# ecg_board.net
KiCad netlist of a schematic drawn in EAGLE
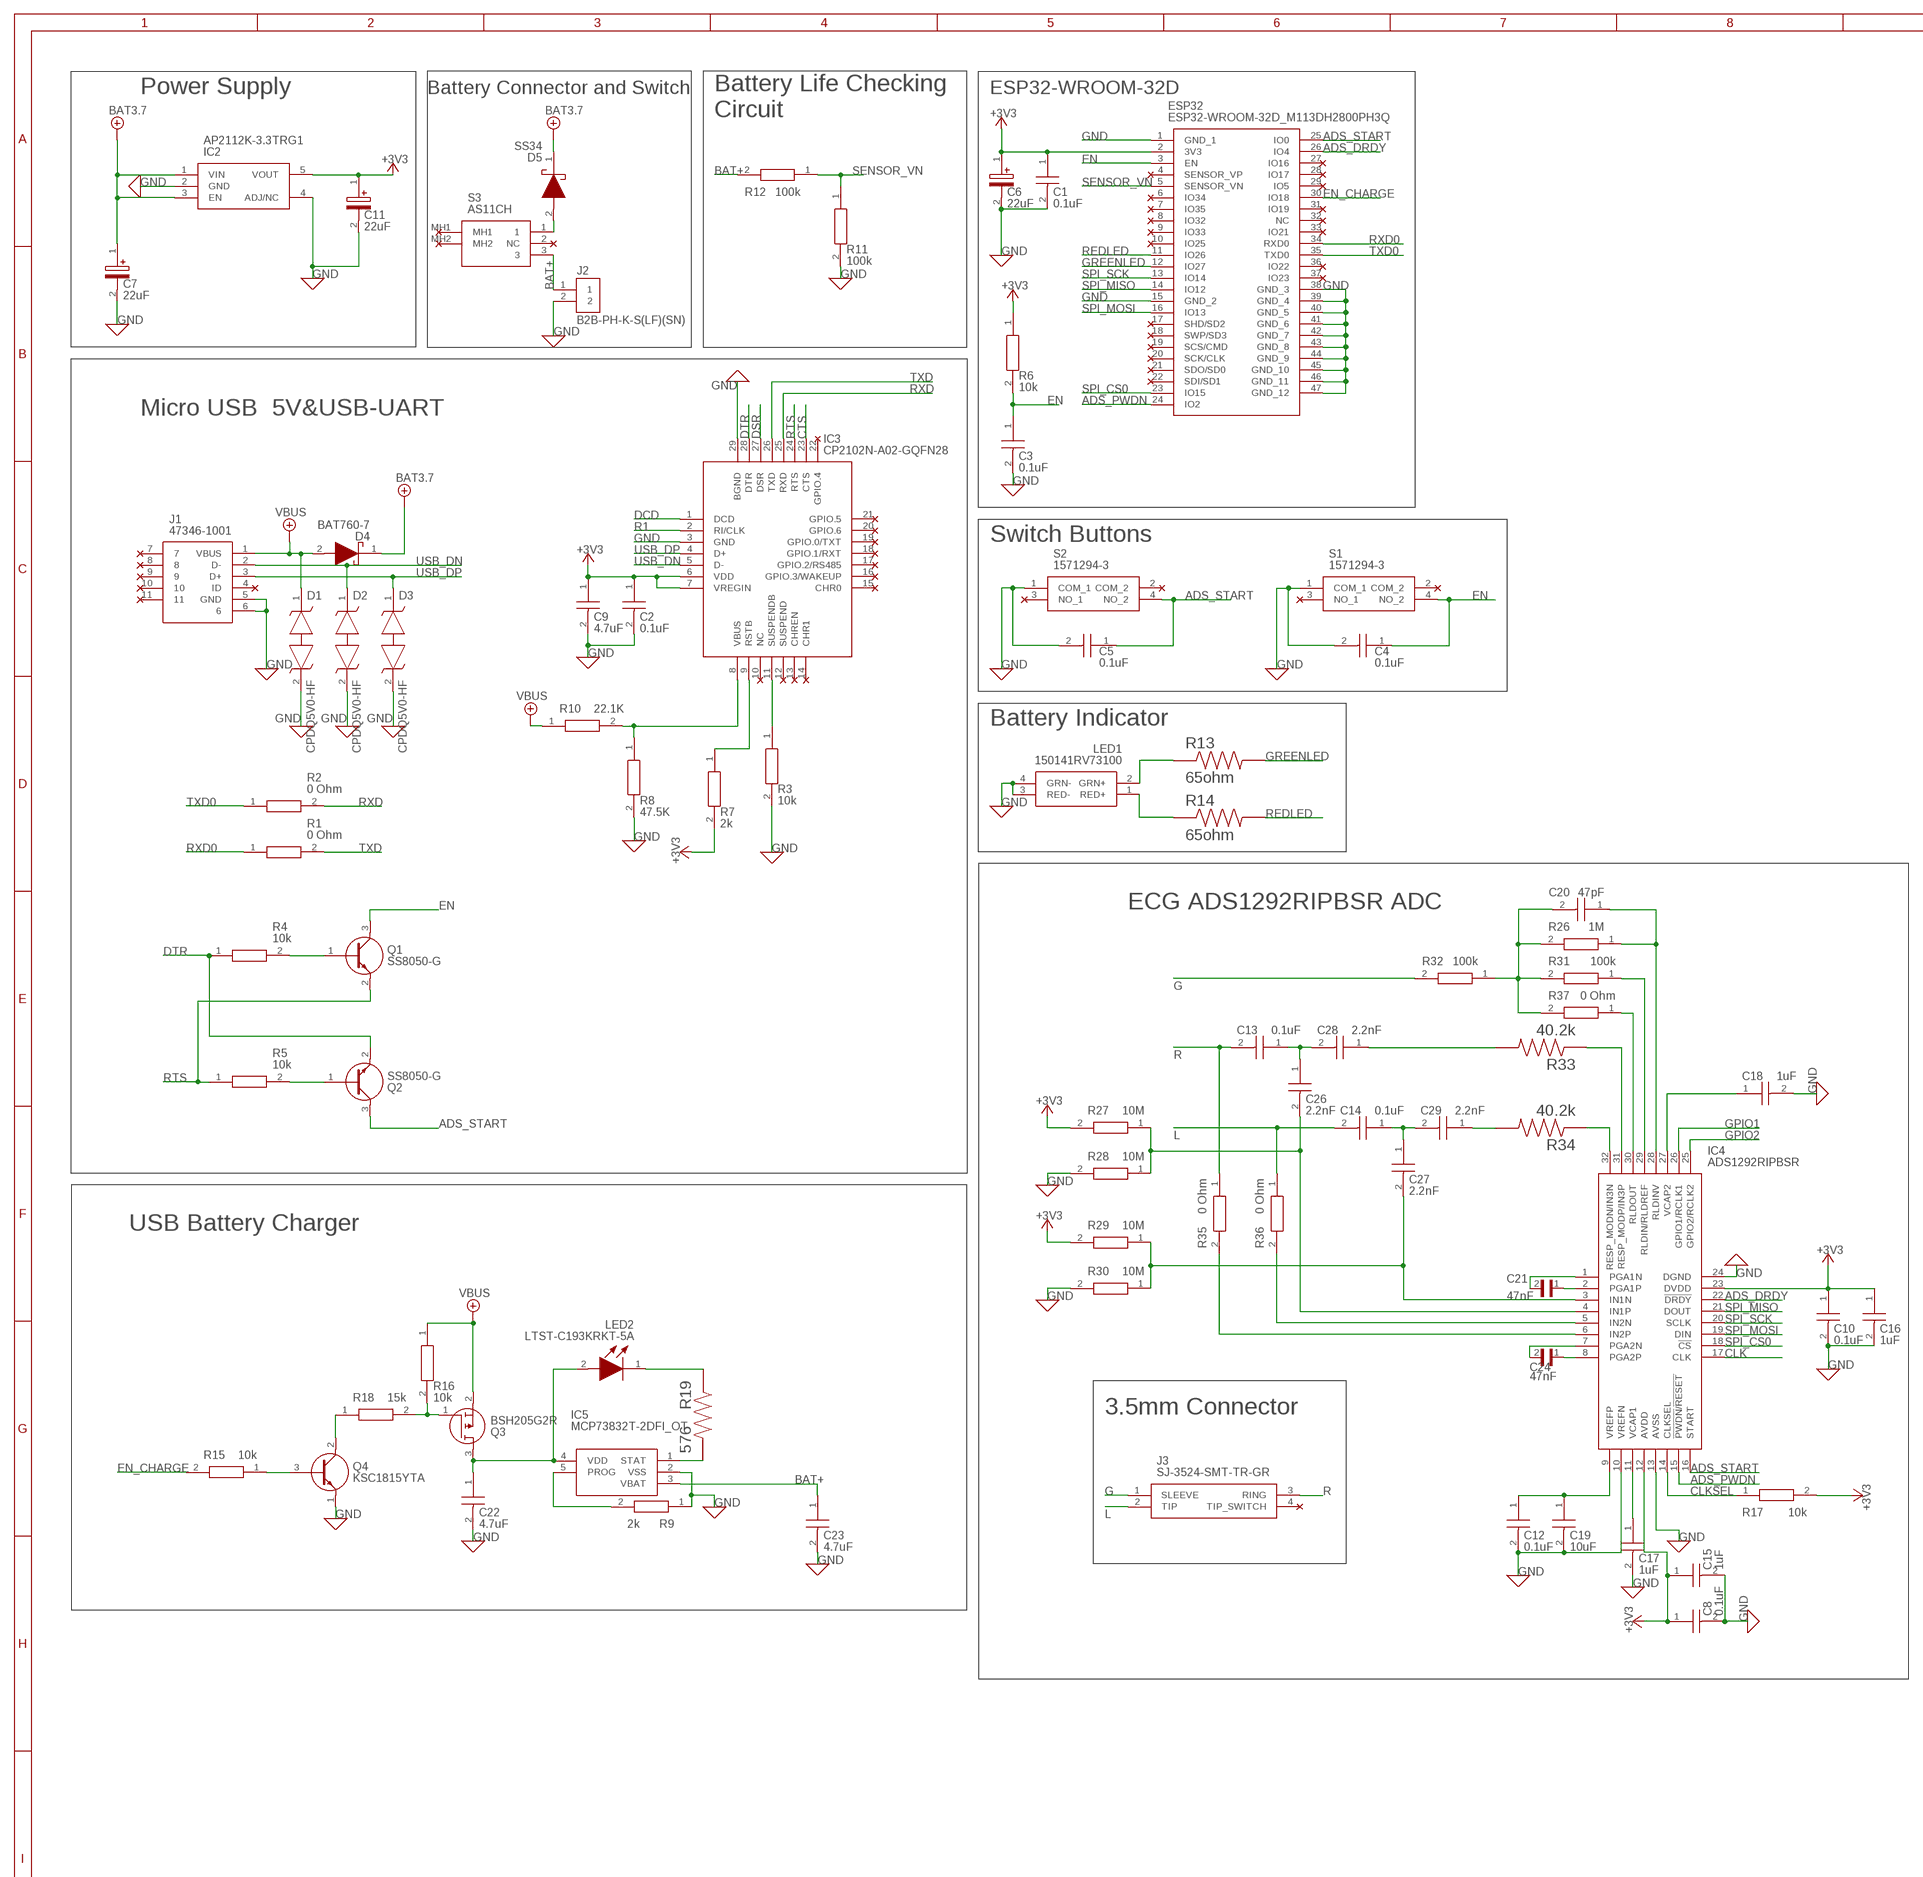
[diagram p0: schematic, sheet 1, part 1 of 2]
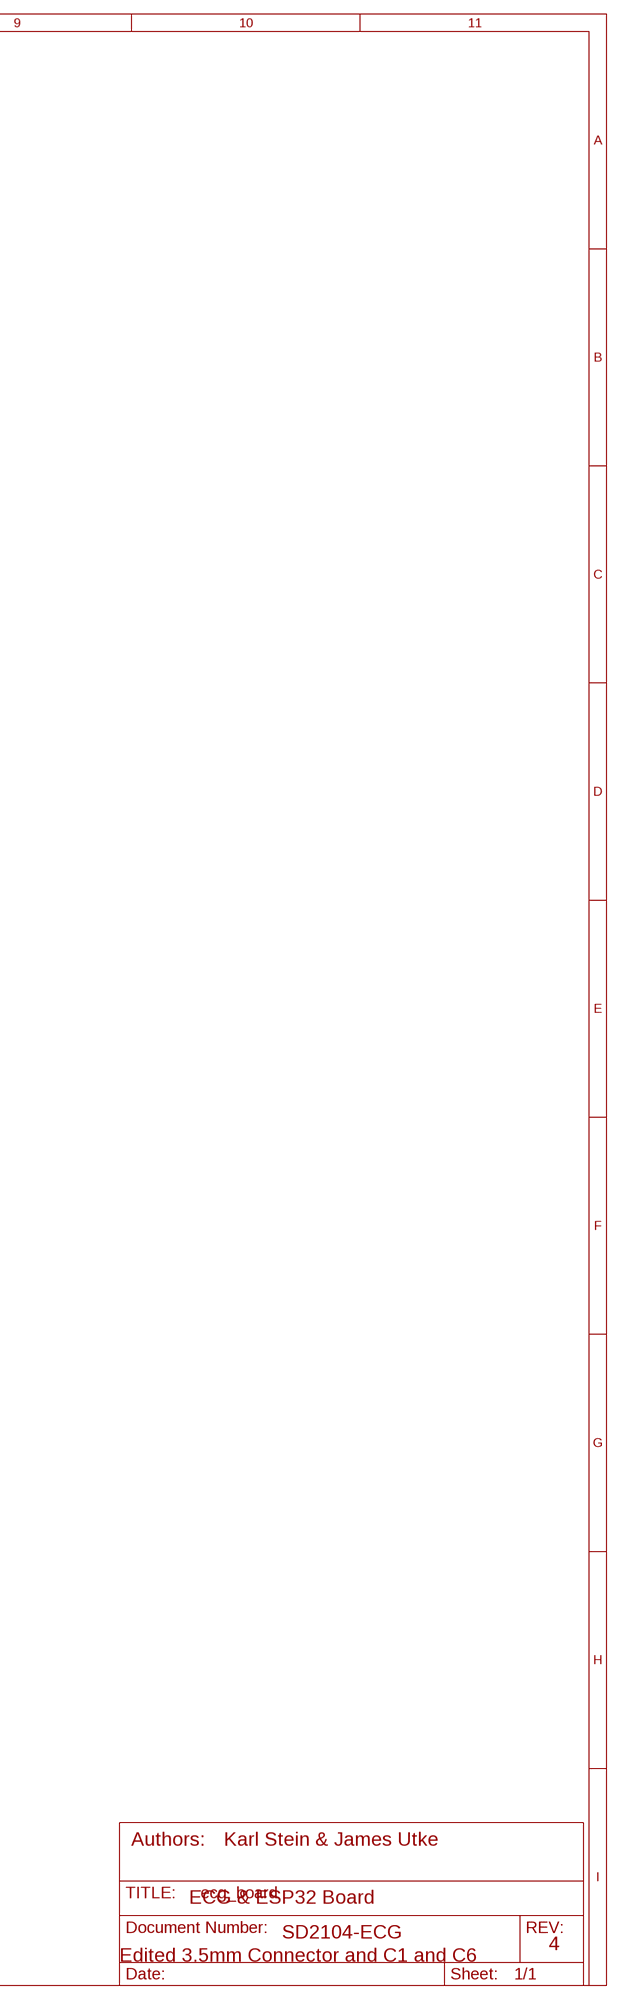
[diagram p1: schematic, sheet 1, part 2 of 2]

(export (version "E")
  (design (tool "Eeschema 10.0.6"))
  (components
    (comp (ref "C1")
      (value "0.1uF")
      (footprint "eagle-import:CAPC2012X88N")
      (fields
        (field (name "MANUFACTURER_PART_NUMBER") "C0805C104K5RAC7411")
        (field (name "MOUSER_PART_NUMBER") "80-C0805C104K5RACLR")
      )
      (libsource (lib "eagle-import") (part "C0805C104K5RAC7411"))
    )
    (comp (ref "C2")
      (value "0.1uF")
      (footprint "eagle-import:CAPC2012X88N")
      (fields
        (field (name "MANUFACTURER_PART_NUMBER") "C0805C104K5RAC7411")
        (field (name "MOUSER_PART_NUMBER") "80-C0805C104K5RACLR")
      )
      (libsource (lib "eagle-import") (part "C0805C104K5RAC7411"))
    )
    (comp (ref "C3")
      (value "0.1uF")
      (footprint "eagle-import:CAPC2012X88N")
      (fields
        (field (name "MANUFACTURER_PART_NUMBER") "C0805C104K5RAC7411")
        (field (name "MOUSER_PART_NUMBER") "80-C0805C104K5RACLR")
      )
      (libsource (lib "eagle-import") (part "C0805C104K5RAC7411"))
    )
    (comp (ref "C4")
      (value "0.1uF")
      (footprint "eagle-import:CAPC2012X88N")
      (fields
        (field (name "MANUFACTURER_PART_NUMBER") "C0805C104K5RAC7411")
        (field (name "MOUSER_PART_NUMBER") "80-C0805C104K5RACLR")
      )
      (libsource (lib "eagle-import") (part "C0805C104K5RAC7411"))
    )
    (comp (ref "C5")
      (value "0.1uF")
      (footprint "eagle-import:CAPC2012X88N")
      (fields
        (field (name "MANUFACTURER_PART_NUMBER") "C0805C104K5RAC7411")
        (field (name "MOUSER_PART_NUMBER") "80-C0805C104K5RACLR")
      )
      (libsource (lib "eagle-import") (part "C0805C104K5RAC7411"))
    )
    (comp (ref "C6")
      (value "22uF")
      (footprint "eagle-import:CAPPC1609X90N")
      (fields
        (field (name "MANUFACTURER_PART_NUMBER") "F381A226MMAAXE")
        (field (name "MOUSER_PART_NUMBER") "581-F381A226MMAAXE")
      )
      (libsource (lib "eagle-import") (part "F381A226MMAAXE"))
    )
    (comp (ref "C7")
      (value "22uF")
      (footprint "eagle-import:CAPPC1609X90N")
      (fields
        (field (name "MANUFACTURER_PART_NUMBER") "F381A226MMAAXE")
        (field (name "MOUSER_PART_NUMBER") "581-F381A226MMAAXE")
      )
      (libsource (lib "eagle-import") (part "F381A226MMAAXE"))
    )
    (comp (ref "C8")
      (value "0.1uF")
      (footprint "eagle-import:CAPC2012X88N")
      (fields
        (field (name "MANUFACTURER_PART_NUMBER") "C0805C104K5RAC7411")
        (field (name "MOUSER_PART_NUMBER") "80-C0805C104K5RACLR")
      )
      (libsource (lib "eagle-import") (part "C0805C104K5RAC7411"))
    )
    (comp (ref "C9")
      (value "4.7uF")
      (footprint "eagle-import:CAPC2114X145N")
      (fields
        (field (name "MANUFACTURER_PART_NUMBER") "JMK212B7475KGHT")
        (field (name "MOUSER_PART_NUMBER") "963-JMK212B7475KGHT")
      )
      (libsource (lib "eagle-import") (part "JMK212B7475KGHT"))
    )
    (comp (ref "C10")
      (value "0.1uF")
      (footprint "eagle-import:CAPC2012X88N")
      (fields
        (field (name "MANUFACTURER_PART_NUMBER") "C0805C104K5RAC7411")
        (field (name "MOUSER_PART_NUMBER") "80-C0805C104K5RACLR")
      )
      (libsource (lib "eagle-import") (part "C0805C104K5RAC7411"))
    )
    (comp (ref "C11")
      (value "22uF")
      (footprint "eagle-import:CAPPC1609X90N")
      (fields
        (field (name "MANUFACTURER_PART_NUMBER") "F381A226MMAAXE")
        (field (name "MOUSER_PART_NUMBER") "581-F381A226MMAAXE")
      )
      (libsource (lib "eagle-import") (part "F381A226MMAAXE"))
    )
    (comp (ref "C12")
      (value "0.1uF")
      (footprint "eagle-import:CAPC2012X88N")
      (fields
        (field (name "MANUFACTURER_PART_NUMBER") "C0805C104K5RAC7411")
        (field (name "MOUSER_PART_NUMBER") "80-C0805C104K5RACLR")
      )
      (libsource (lib "eagle-import") (part "C0805C104K5RAC7411"))
    )
    (comp (ref "C13")
      (value "0.1uF")
      (footprint "eagle-import:CAPC2012X88N")
      (fields
        (field (name "MANUFACTURER_PART_NUMBER") "C0805C104K5RAC7411")
        (field (name "MOUSER_PART_NUMBER") "80-C0805C104K5RACLR")
      )
      (libsource (lib "eagle-import") (part "C0805C104K5RAC7411"))
    )
    (comp (ref "C14")
      (value "0.1uF")
      (footprint "eagle-import:CAPC2012X88N")
      (fields
        (field (name "MANUFACTURER_PART_NUMBER") "C0805C104K5RAC7411")
        (field (name "MOUSER_PART_NUMBER") "80-C0805C104K5RACLR")
      )
      (libsource (lib "eagle-import") (part "C0805C104K5RAC7411"))
    )
    (comp (ref "C15")
      (value "1uF")
      (footprint "eagle-import:CAPC2012X100N")
      (fields
        (field (name "MANUFACTURER_PART_NUMBER") "C0805X105K8RAC7210")
        (field (name "MOUSER_PART_NUMBER") "80-C0805X105K8RACLR")
      )
      (libsource (lib "eagle-import") (part "C0805X105K8RAC7210"))
    )
    (comp (ref "C16")
      (value "1uF")
      (footprint "eagle-import:CAPC2012X100N")
      (fields
        (field (name "MANUFACTURER_PART_NUMBER") "C0805X105K8RAC7210")
        (field (name "MOUSER_PART_NUMBER") "80-C0805X105K8RACLR")
      )
      (libsource (lib "eagle-import") (part "C0805X105K8RAC7210"))
    )
    (comp (ref "C17")
      (value "1uF")
      (footprint "eagle-import:CAPC2012X100N")
      (fields
        (field (name "MANUFACTURER_PART_NUMBER") "C0805X105K8RAC7210")
        (field (name "MOUSER_PART_NUMBER") "80-C0805X105K8RACLR")
      )
      (libsource (lib "eagle-import") (part "C0805X105K8RAC7210"))
    )
    (comp (ref "C18")
      (value "1uF")
      (footprint "eagle-import:CAPC2012X100N")
      (fields
        (field (name "MANUFACTURER_PART_NUMBER") "C0805X105K8RAC7210")
        (field (name "MOUSER_PART_NUMBER") "80-C0805X105K8RACLR")
      )
      (libsource (lib "eagle-import") (part "C0805X105K8RAC7210"))
    )
    (comp (ref "C19")
      (value "10uF")
      (footprint "eagle-import:CAPC2012X135N")
      (fields
        (field (name "MANUFACTURER_PART_NUMBER") "TMK212BBJ106MGHT")
        (field (name "MOUSER_PART_NUMBER") "963-TMK212BBJ106MGHT")
      )
      (libsource (lib "eagle-import") (part "TMK212BBJ106MGHT"))
    )
    (comp (ref "C20")
      (value "47pF")
      (footprint "eagle-import:CAPC2012X95N")
      (fields
        (field (name "MANUFACTURER_PART_NUMBER") "CBR08C470J5GAC")
        (field (name "MOUSER_PART_NUMBER") "80-CBR08C470J5GAC")
      )
      (libsource (lib "eagle-import") (part "CBR08C470J5GAC"))
    )
    (comp (ref "C21")
      (value "47nF")
      (footprint "eagle-import:CAPC2012X140N")
      (fields
        (field (name "DIGI-KEY_PART_NUMBER") "399-C0805C473K1RECAUTOCT-ND")
        (field (name "MF") "KEMET")
        (field (name "MP") "C0805C473K1RECAUTO")
      )
      (libsource (lib "eagle-import") (part "C0805C473K1RECAUTO"))
    )
    (comp (ref "C22")
      (value "4.7uF")
      (footprint "eagle-import:CAPC2114X145N")
      (fields
        (field (name "MANUFACTURER_PART_NUMBER") "JMK212B7475KGHT")
        (field (name "MOUSER_PART_NUMBER") "963-JMK212B7475KGHT")
      )
      (libsource (lib "eagle-import") (part "JMK212B7475KGHT"))
    )
    (comp (ref "C23")
      (value "4.7uF")
      (footprint "eagle-import:CAPC2114X145N")
      (fields
        (field (name "MANUFACTURER_PART_NUMBER") "JMK212B7475KGHT")
        (field (name "MOUSER_PART_NUMBER") "963-JMK212B7475KGHT")
      )
      (libsource (lib "eagle-import") (part "JMK212B7475KGHT"))
    )
    (comp (ref "C24")
      (value "47nF")
      (footprint "eagle-import:CAPC2012X140N")
      (fields
        (field (name "DIGI-KEY_PART_NUMBER") "399-C0805C473K1RECAUTOCT-ND")
        (field (name "MF") "KEMET")
        (field (name "MP") "C0805C473K1RECAUTO")
      )
      (libsource (lib "eagle-import") (part "C0805C473K1RECAUTO"))
    )
    (comp (ref "C26")
      (value "2.2nF")
      (footprint "eagle-import:CAPC2012X100N")
      (fields
        (field (name "MANUFACTURER_PART_NUMBER") "C0805J222K1RACAUTO")
        (field (name "MOUSER_PART_NUMBER") "80-C0805J222K1RAUTO")
      )
      (libsource (lib "eagle-import") (part "C0805J222K1RACAUTO"))
    )
    (comp (ref "C27")
      (value "2.2nF")
      (footprint "eagle-import:CAPC2012X100N")
      (fields
        (field (name "MANUFACTURER_PART_NUMBER") "C0805J222K1RACAUTO")
        (field (name "MOUSER_PART_NUMBER") "80-C0805J222K1RAUTO")
      )
      (libsource (lib "eagle-import") (part "C0805J222K1RACAUTO"))
    )
    (comp (ref "C28")
      (value "2.2nF")
      (footprint "eagle-import:CAPC2012X100N")
      (fields
        (field (name "MANUFACTURER_PART_NUMBER") "C0805J222K1RACAUTO")
        (field (name "MOUSER_PART_NUMBER") "80-C0805J222K1RAUTO")
      )
      (libsource (lib "eagle-import") (part "C0805J222K1RACAUTO"))
    )
    (comp (ref "C29")
      (value "2.2nF")
      (footprint "eagle-import:CAPC2012X100N")
      (fields
        (field (name "MANUFACTURER_PART_NUMBER") "C0805J222K1RACAUTO")
        (field (name "MOUSER_PART_NUMBER") "80-C0805J222K1RAUTO")
      )
      (libsource (lib "eagle-import") (part "C0805J222K1RACAUTO"))
    )
    (comp (ref "D1")
      (value "CPDQ5V0-HF")
      (footprint "eagle-import:SODFL1006X40N")
      (fields (field (name "MOUSER_PART_NUMBER") "750-CPDQ5V0-HF"))
      (libsource (lib "eagle-import") (part "CPDQ5V0-HF"))
    )
    (comp (ref "D2")
      (value "CPDQ5V0-HF")
      (footprint "eagle-import:SODFL1006X40N")
      (fields (field (name "MOUSER_PART_NUMBER") "750-CPDQ5V0-HF"))
      (libsource (lib "eagle-import") (part "CPDQ5V0-HF"))
    )
    (comp (ref "D3")
      (value "CPDQ5V0-HF")
      (footprint "eagle-import:SODFL1006X40N")
      (fields (field (name "MOUSER_PART_NUMBER") "750-CPDQ5V0-HF"))
      (libsource (lib "eagle-import") (part "CPDQ5V0-HF"))
    )
    (comp (ref "D4")
      (value "BAT760-7")
      (footprint "eagle-import:SOD2513X120N")
      (fields (field (name "MOUSER_PART_NUMBER") "621-BAT760-7"))
      (libsource (lib "eagle-import") (part "BAT760-7"))
    )
    (comp (ref "D5")
      (value "SS34")
      (footprint "eagle-import:DIOM8059X256N")
      (fields (field (name "MOUSER_PART_NUMBER") "512-SS34"))
      (libsource (lib "eagle-import") (part "SS34"))
    )
    (comp (ref "ESP32")
      (value "ESP32-WROOM-32D_M113DH2800PH3Q")
      (footprint "eagle-import:ESP32WROOM32DM113DH2800PH3Q0")
      (fields
        (field (name "MANUFACTURER_PART_NUMBER") "ESP32-WROOM-32D(M113DH2800PH3Q0)")
        (field (name "MOUSER_PART_NUMBER") "356-ES32WROOM32D16MB")
      )
      (libsource (lib "eagle-import") (part "ESP32-WROOM-32D_M113DH2800PH3Q"))
    )
    (comp (ref "IC2")
      (value "AP2112K-3.3TRG1")
      (footprint "eagle-import:SOT95P282X130-5N")
      (fields (field (name "MOUSER_PART_NUMBER") "621-AP2112K-3.3TRG1"))
      (libsource (lib "eagle-import") (part "AP2112K-3.3TRG1"))
    )
    (comp (ref "IC3")
      (value "CP2102N-A02-GQFN28")
      (footprint "eagle-import:QFN50P500X500X80-29N")
      (fields (field (name "MOUSER_PART_NUMBER") "634-CP2102NA02GQFN28"))
      (libsource (lib "eagle-import") (part "CP2102N-A02-GQFN28"))
    )
    (comp (ref "IC4")
      (value "ADS1292RIPBSR")
      (footprint "eagle-import:QFP50P700X700X120-32N")
      (fields (field (name "MOUSER_PART_NUMBER") "595-ADS1292RIPBSR"))
      (libsource (lib "eagle-import") (part "ADS1292RIPBSR"))
    )
    (comp (ref "IC5")
      (value "MCP73832T-2DFI_OT")
      (footprint "eagle-import:SOT95P270X145-5N")
      (fields
        (field (name "MANUFACTURER_PART_NUMBER") "MCP73832T-2DFI/OT")
        (field (name "MOUSER_PART_NUMBER") "579-MCP73832T2DFI/OT")
      )
      (libsource (lib "eagle-import") (part "MCP73832T-2DFI_OT"))
    )
    (comp (ref "J1")
      (value "47346-1001")
      (footprint "eagle-import:473461001")
      (fields (field (name "MOUSER_PART_NUMBER") "538-47346-1001"))
      (libsource (lib "eagle-import") (part "47346-1001"))
    )
    (comp (ref "J2")
      (value "B2B-PH-K-S(LF)(SN)")
      (footprint "eagle-import:JST_B2B-PH-K-S(LF)(SN)")
      (fields (field (name "DIGI-KEY_PART_NUMBER") "455-1704-ND") (field (name "MF") "JST Sales"))
      (libsource (lib "eagle-import") (part "B2B-PH-K-S(LF)(SN)"))
    )
    (comp (ref "J3")
      (value "SJ-3524-SMT-TR-GR")
      (footprint "eagle-import:SJ3524SMTTRGR")
      (fields (field (name "MOUSER_PART_NUMBER") "490-SJ3524-SMT-TR-GR"))
      (libsource (lib "eagle-import") (part "SJ-3524-SMT-TR-GR"))
    )
    (comp (ref "LED1")
      (value "150141RV73100")
      (footprint "eagle-import:SMD3528_1")
      (fields (field (name "MOUSER_PART_NUMBER") "710-150141RV73100"))
      (libsource (lib "eagle-import") (part "150141RV73100"))
    )
    (comp (ref "LED2")
      (value "LTST-C193KRKT-5A")
      (footprint "eagle-import:LEDC1608X45N")
      (fields (field (name "MOUSER_PART_NUMBER") "859-LTSTC193KRKT5A"))
      (libsource (lib "eagle-import") (part "LTST-C193KRKT-5A"))
    )
    (comp (ref "Q1")
      (value "SS8050-G")
      (footprint "eagle-import:SOT95P240X115-3N")
      (fields (field (name "MOUSER_PART_NUMBER") "750-SS8050-G"))
      (libsource (lib "eagle-import") (part "SS8050-G"))
    )
    (comp (ref "Q2")
      (value "SS8050-G")
      (footprint "eagle-import:SOT95P240X115-3N")
      (fields (field (name "MOUSER_PART_NUMBER") "750-SS8050-G"))
      (libsource (lib "eagle-import") (part "SS8050-G"))
    )
    (comp (ref "Q3")
      (value "BSH205G2R")
      (footprint "eagle-import:SOT95P230X110-3N")
      (fields (field (name "MOUSER_PART_NUMBER") "771-BSH205G2R"))
      (libsource (lib "eagle-import") (part "BSH205G2R"))
    )
    (comp (ref "Q4")
      (value "KSC1815YTA")
      (footprint "eagle-import:BC33740TA")
      (fields (field (name "MOUSER_PART_NUMBER") "512-KSC1815YTA"))
      (libsource (lib "eagle-import") (part "KSC1815YTA"))
    )
    (comp (ref "R1")
      (value "0 Ohm")
      (footprint "eagle-import:RESC1608X55N")
      (fields
        (field (name "MANUFACTURER_PART_NUMBER") "CR0603AJ/-000ELF")
        (field (name "MOUSER_PART_NUMBER") "652-CR0603AJ/-000ELF")
      )
      (libsource (lib "eagle-import") (part "CR0603AJ_-000ELF"))
    )
    (comp (ref "R2")
      (value "0 Ohm")
      (footprint "eagle-import:RESC1608X55N")
      (fields
        (field (name "MANUFACTURER_PART_NUMBER") "CR0603AJ/-000ELF")
        (field (name "MOUSER_PART_NUMBER") "652-CR0603AJ/-000ELF")
      )
      (libsource (lib "eagle-import") (part "CR0603AJ_-000ELF"))
    )
    (comp (ref "R3")
      (value "10k")
      (footprint "eagle-import:CAPC1608X55N")
      (fields
        (field (name "MANUFACTURER_PART_NUMBER") "HV73V1JTTD103J")
        (field (name "MOUSER_PART_NUMBER") "660-HV73V1JTTD103J")
      )
      (libsource (lib "eagle-import") (part "HV73V1JTTD103J"))
    )
    (comp (ref "R4")
      (value "10k")
      (footprint "eagle-import:CAPC1608X55N")
      (fields
        (field (name "MANUFACTURER_PART_NUMBER") "HV73V1JTTD103J")
        (field (name "MOUSER_PART_NUMBER") "660-HV73V1JTTD103J")
      )
      (libsource (lib "eagle-import") (part "HV73V1JTTD103J"))
    )
    (comp (ref "R5")
      (value "10k")
      (footprint "eagle-import:CAPC1608X55N")
      (fields
        (field (name "MANUFACTURER_PART_NUMBER") "HV73V1JTTD103J")
        (field (name "MOUSER_PART_NUMBER") "660-HV73V1JTTD103J")
      )
      (libsource (lib "eagle-import") (part "HV73V1JTTD103J"))
    )
    (comp (ref "R6")
      (value "10k")
      (footprint "eagle-import:CAPC1608X55N")
      (fields
        (field (name "MANUFACTURER_PART_NUMBER") "HV73V1JTTD103J")
        (field (name "MOUSER_PART_NUMBER") "660-HV73V1JTTD103J")
      )
      (libsource (lib "eagle-import") (part "HV73V1JTTD103J"))
    )
    (comp (ref "R7")
      (value "2k")
      (footprint "eagle-import:RESC1608X55N")
      (fields (field (name "MANUFACTURER_PART_NUMBER") "ERJ-UP3F2001V"))
      (libsource (lib "eagle-import") (part "ERJ-UP3F2001V"))
    )
    (comp (ref "R8")
      (value "47.5K")
      (footprint "eagle-import:RESC1608X55N")
      (fields
        (field (name "MANUFACTURER_PART_NUMBER") "ERJ-UP3F4752V")
        (field (name "MOUSER_PART_NUMBER") "667-ERJ-UP3F4752V")
      )
      (libsource (lib "eagle-import") (part "ERJ-UP3F4752V"))
    )
    (comp (ref "R9")
      (value "2k")
      (footprint "eagle-import:RESC1608X55N")
      (fields (field (name "MANUFACTURER_PART_NUMBER") "ERJ-UP3F2001V"))
      (libsource (lib "eagle-import") (part "ERJ-UP3F2001V"))
    )
    (comp (ref "R10")
      (value "22.1K")
      (footprint "eagle-import:RESC1005X40N")
      (fields
        (field (name "MANUFACTURER_PART_NUMBER") "ERJ-2RHD2212X")
        (field (name "MOUSER_PART_NUMBER") "667-ERJ-2RHD2212X")
      )
      (libsource (lib "eagle-import") (part "ERJ-2RHD2212X"))
    )
    (comp (ref "R11")
      (value "100k")
      (footprint "eagle-import:RESC1608X50N")
      (fields
        (field (name "MANUFACTURER_PART_NUMBER") "RCG0603100KJNEA")
        (field (name "MOUSER_PART_NUMBER") "71-RCG0603100KJNEA")
      )
      (libsource (lib "eagle-import") (part "RCG0603100KJNEA"))
    )
    (comp (ref "R12")
      (value "100k")
      (footprint "eagle-import:RESC1608X50N")
      (fields
        (field (name "MANUFACTURER_PART_NUMBER") "RCG0603100KJNEA")
        (field (name "MOUSER_PART_NUMBER") "71-RCG0603100KJNEA")
      )
      (libsource (lib "eagle-import") (part "RCG0603100KJNEA"))
    )
    (comp (ref "R13")
      (value "65ohm")
      (footprint "eagle-import:RESC2012X64N")
      (fields
        (field (name "DIGI-KEY_PART_NUMBER") "Y402265R0000A9W-ND")
        (field (name "MF") "Vishay")
        (field (name "MP") "Y402265R0000A9W")
      )
      (libsource (lib "eagle-import") (part "Y402265R0000A9W"))
    )
    (comp (ref "R14")
      (value "65ohm")
      (footprint "eagle-import:RESC2012X64N")
      (fields
        (field (name "DIGI-KEY_PART_NUMBER") "Y402265R0000A9W-ND")
        (field (name "MF") "Vishay")
        (field (name "MP") "Y402265R0000A9W")
      )
      (libsource (lib "eagle-import") (part "Y402265R0000A9W"))
    )
    (comp (ref "R15")
      (value "10k")
      (footprint "eagle-import:CAPC1608X55N")
      (fields
        (field (name "MANUFACTURER_PART_NUMBER") "HV73V1JTTD103J")
        (field (name "MOUSER_PART_NUMBER") "660-HV73V1JTTD103J")
      )
      (libsource (lib "eagle-import") (part "HV73V1JTTD103J"))
    )
    (comp (ref "R16")
      (value "10k")
      (footprint "eagle-import:CAPC1608X55N")
      (fields
        (field (name "MANUFACTURER_PART_NUMBER") "HV73V1JTTD103J")
        (field (name "MOUSER_PART_NUMBER") "660-HV73V1JTTD103J")
      )
      (libsource (lib "eagle-import") (part "HV73V1JTTD103J"))
    )
    (comp (ref "R17")
      (value "10k")
      (footprint "eagle-import:CAPC1608X55N")
      (fields
        (field (name "MANUFACTURER_PART_NUMBER") "HV73V1JTTD103J")
        (field (name "MOUSER_PART_NUMBER") "660-HV73V1JTTD103J")
      )
      (libsource (lib "eagle-import") (part "HV73V1JTTD103J"))
    )
    (comp (ref "R18")
      (value "15k")
      (footprint "eagle-import:RESC2012X60N")
      (fields
        (field (name "MANUFACTURER_PART_NUMBER") "CRCW080515K0FKEBC")
        (field (name "MOUSER_PART_NUMBER") "71-CRCW080515K0FKEBC")
      )
      (libsource (lib "eagle-import") (part "CRCW080515K0FKEBC"))
    )
    (comp (ref "R19")
      (value "576")
      (footprint "eagle-import:RESC2012X50N")
      (fields
        (field (name "DIGI-KEY_PART_NUMBER") "541-576CCT-ND")
        (field (name "MF") "Vishay")
        (field (name "MP") "CRCW0805576RFKEA")
      )
      (libsource (lib "eagle-import") (part "CRCW0805576RFKEA"))
    )
    (comp (ref "R26")
      (value "1M")
      (footprint "eagle-import:RESC1608X55N")
      (fields (field (name "MANUFACTURER_PART_NUMBER") "HV731JTTD105J"))
      (libsource (lib "eagle-import") (part "HV731JTTD105J"))
    )
    (comp (ref "R27")
      (value "10M")
      (footprint "eagle-import:RESC1608X55N")
      (fields
        (field (name "MANUFACTURER_PART_NUMBER") "CRCW060310M0JNEAC")
        (field (name "MOUSER_PART_NUMBER") "71-CRCW060310M0JNEAC")
      )
      (libsource (lib "eagle-import") (part "CRCW060310M0JNEAC"))
    )
    (comp (ref "R28")
      (value "10M")
      (footprint "eagle-import:RESC1608X55N")
      (fields
        (field (name "MANUFACTURER_PART_NUMBER") "CRCW060310M0JNEAC")
        (field (name "MOUSER_PART_NUMBER") "71-CRCW060310M0JNEAC")
      )
      (libsource (lib "eagle-import") (part "CRCW060310M0JNEAC"))
    )
    (comp (ref "R29")
      (value "10M")
      (footprint "eagle-import:RESC1608X55N")
      (fields
        (field (name "MANUFACTURER_PART_NUMBER") "CRCW060310M0JNEAC")
        (field (name "MOUSER_PART_NUMBER") "71-CRCW060310M0JNEAC")
      )
      (libsource (lib "eagle-import") (part "CRCW060310M0JNEAC"))
    )
    (comp (ref "R30")
      (value "10M")
      (footprint "eagle-import:RESC1608X55N")
      (fields
        (field (name "MANUFACTURER_PART_NUMBER") "CRCW060310M0JNEAC")
        (field (name "MOUSER_PART_NUMBER") "71-CRCW060310M0JNEAC")
      )
      (libsource (lib "eagle-import") (part "CRCW060310M0JNEAC"))
    )
    (comp (ref "R31")
      (value "100k")
      (footprint "eagle-import:RESC1608X50N")
      (fields
        (field (name "MANUFACTURER_PART_NUMBER") "RCG0603100KJNEA")
        (field (name "MOUSER_PART_NUMBER") "71-RCG0603100KJNEA")
      )
      (libsource (lib "eagle-import") (part "RCG0603100KJNEA"))
    )
    (comp (ref "R32")
      (value "100k")
      (footprint "eagle-import:RESC1608X50N")
      (fields
        (field (name "MANUFACTURER_PART_NUMBER") "RCG0603100KJNEA")
        (field (name "MOUSER_PART_NUMBER") "71-RCG0603100KJNEA")
      )
      (libsource (lib "eagle-import") (part "RCG0603100KJNEA"))
    )
    (comp (ref "R33")
      (value "40.2k")
      (footprint "eagle-import:RESC3216X70N")
      (fields
        (field (name "DIGI-KEY_PART_NUMBER") "RMCF1206FT40K2CT-ND")
        (field (name "MF") "Stackpole Electronics Inc")
        (field (name "MP") "RMCF1206FT40K2")
      )
      (libsource (lib "eagle-import") (part "RMCF1206FT40K2"))
    )
    (comp (ref "R34")
      (value "40.2k")
      (footprint "eagle-import:RESC3216X70N")
      (fields
        (field (name "DIGI-KEY_PART_NUMBER") "RMCF1206FT40K2CT-ND")
        (field (name "MF") "Stackpole Electronics Inc")
        (field (name "MP") "RMCF1206FT40K2")
      )
      (libsource (lib "eagle-import") (part "RMCF1206FT40K2"))
    )
    (comp (ref "R35")
      (value "0 Ohm")
      (footprint "eagle-import:RESC1608X55N")
      (fields
        (field (name "MANUFACTURER_PART_NUMBER") "CR0603AJ/-000ELF")
        (field (name "MOUSER_PART_NUMBER") "652-CR0603AJ/-000ELF")
      )
      (libsource (lib "eagle-import") (part "CR0603AJ_-000ELF"))
    )
    (comp (ref "R36")
      (value "0 Ohm")
      (footprint "eagle-import:RESC1608X55N")
      (fields
        (field (name "MANUFACTURER_PART_NUMBER") "CR0603AJ/-000ELF")
        (field (name "MOUSER_PART_NUMBER") "652-CR0603AJ/-000ELF")
      )
      (libsource (lib "eagle-import") (part "CR0603AJ_-000ELF"))
    )
    (comp (ref "R37")
      (value "0 Ohm")
      (footprint "eagle-import:RESC1608X55N")
      (fields
        (field (name "MANUFACTURER_PART_NUMBER") "CR0603AJ/-000ELF")
        (field (name "MOUSER_PART_NUMBER") "652-CR0603AJ/-000ELF")
      )
      (libsource (lib "eagle-import") (part "CR0603AJ_-000ELF"))
    )
    (comp (ref "S1")
      (value "1571294-3")
      (footprint "eagle-import:15712943")
      (fields (field (name "MOUSER_PART_NUMBER") "506-1571294-3"))
      (libsource (lib "eagle-import") (part "1571294-3"))
    )
    (comp (ref "S2")
      (value "1571294-3")
      (footprint "eagle-import:15712943")
      (fields (field (name "MOUSER_PART_NUMBER") "506-1571294-3"))
      (libsource (lib "eagle-import") (part "1571294-3"))
    )
    (comp (ref "S3")
      (value "AS11CH")
      (footprint "eagle-import:AS11CH")
      (fields (field (name "MOUSER_PART_NUMBER") "633-AS11CH"))
      (libsource (lib "eagle-import") (part "AS11CH"))
    )
  )
  (nets
    (net (code "1") (name "+3V3") (class "Default")
      (node (ref "C1") (pin "1") (pinfunction "1_1") (pintype "bidirectional"))
      (node (ref "C10") (pin "1") (pinfunction "1_1") (pintype "bidirectional"))
      (node (ref "C11") (pin "1") (pinfunction "+_1") (pintype "bidirectional"))
      (node (ref "C15") (pin "1") (pinfunction "1_1") (pintype "bidirectional"))
      (node (ref "C16") (pin "1") (pinfunction "1_1") (pintype "bidirectional"))
      (node (ref "C2") (pin "1") (pinfunction "1_1") (pintype "bidirectional"))
      (node (ref "C6") (pin "1") (pinfunction "+_1") (pintype "bidirectional"))
      (node (ref "C8") (pin "1") (pinfunction "1_1") (pintype "bidirectional"))
      (node (ref "C9") (pin "1") (pinfunction "1_1") (pintype "bidirectional"))
      (node (ref "ESP32") (pin "2") (pinfunction "3V3_2") (pintype "bidirectional"))
      (node (ref "IC2") (pin "5") (pinfunction "VOUT_5") (pintype "bidirectional"))
      (node (ref "IC3") (pin "6") (pinfunction "VDD_6") (pintype "power_in"))
      (node (ref "IC3") (pin "7") (pinfunction "VREGIN_7") (pintype "power_in"))
      (node (ref "IC4") (pin "12") (pinfunction "AVDD_12") (pintype "bidirectional"))
      (node (ref "IC4") (pin "23") (pinfunction "DVDD_23") (pintype "bidirectional"))
      (node (ref "R17") (pin "2") (pinfunction "2_2") (pintype "bidirectional"))
      (node (ref "R27") (pin "2") (pinfunction "2_2") (pintype "bidirectional"))
      (node (ref "R29") (pin "2") (pinfunction "2_2") (pintype "bidirectional"))
      (node (ref "R6") (pin "1") (pinfunction "1_1") (pintype "bidirectional"))
      (node (ref "R7") (pin "2") (pinfunction "2_2") (pintype "bidirectional"))
    )
    (net (code "2") (name "/ADS_DRDY") (class "Default")
      (node (ref "ESP32") (pin "26") (pinfunction "IO4_26") (pintype "bidirectional"))
      (node (ref "IC4") (pin "22") (pinfunction "~{DRDY}_22") (pintype "bidirectional"))
    )
    (net (code "3") (name "/ADS_PWDN") (class "Default")
      (node (ref "ESP32") (pin "24") (pinfunction "IO2_24") (pintype "bidirectional"))
      (node (ref "IC4") (pin "15") (pinfunction "~{PWDN}/~{RESET}_15") (pintype "bidirectional"))
    )
    (net (code "4") (name "/ADS_START") (class "Default")
      (node (ref "C5") (pin "1") (pinfunction "1_1") (pintype "bidirectional"))
      (node (ref "ESP32") (pin "25") (pinfunction "IO0_25") (pintype "bidirectional"))
      (node (ref "IC4") (pin "16") (pinfunction "START_16") (pintype "bidirectional"))
      (node (ref "Q2") (pin "3") (pinfunction "C_3") (pintype "bidirectional"))
      (node (ref "S2") (pin "4") (pinfunction "NO_2_4") (pintype "bidirectional"))
    )
    (net (code "5") (name "/BAT+") (class "Default")
      (node (ref "C23") (pin "1") (pinfunction "1_1") (pintype "bidirectional"))
      (node (ref "IC5") (pin "3") (pinfunction "VBAT_3") (pintype "bidirectional"))
      (node (ref "J2") (pin "1") (pinfunction "1_1") (pintype "passive"))
      (node (ref "R12") (pin "2") (pinfunction "2_2") (pintype "bidirectional"))
      (node (ref "S3") (pin "3") (pinfunction "3_3") (pintype "bidirectional"))
    )
    (net (code "6") (name "/CLK") (class "Default")
      (node (ref "IC4") (pin "17") (pinfunction "CLK_17") (pintype "bidirectional"))
    )
    (net (code "7") (name "/CLKSEL") (class "Default")
      (node (ref "IC4") (pin "14") (pinfunction "CLKSEL_14") (pintype "bidirectional"))
      (node (ref "R17") (pin "1") (pinfunction "1_1") (pintype "bidirectional"))
    )
    (net (code "8") (name "/CTS") (class "Default")
      (node (ref "IC3") (pin "23") (pinfunction "CTS_23") (pintype "input"))
    )
    (net (code "9") (name "/DCD") (class "Default")
      (node (ref "IC3") (pin "1") (pinfunction "DCD_1") (pintype "input"))
    )
    (net (code "10") (name "/DSR") (class "Default")
      (node (ref "IC3") (pin "27") (pinfunction "DSR_27") (pintype "input"))
    )
    (net (code "11") (name "/DTR") (class "Default")
      (node (ref "IC3") (pin "28") (pinfunction "DTR_28") (pintype "output"))
      (node (ref "Q2") (pin "2") (pinfunction "E_2") (pintype "bidirectional"))
      (node (ref "R4") (pin "1") (pinfunction "1_1") (pintype "bidirectional"))
    )
    (net (code "12") (name "/EN") (class "Default")
      (node (ref "C3") (pin "1") (pinfunction "1_1") (pintype "bidirectional"))
      (node (ref "C4") (pin "1") (pinfunction "1_1") (pintype "bidirectional"))
      (node (ref "ESP32") (pin "3") (pinfunction "EN_3") (pintype "bidirectional"))
      (node (ref "Q1") (pin "3") (pinfunction "C_3") (pintype "bidirectional"))
      (node (ref "R6") (pin "2") (pinfunction "2_2") (pintype "bidirectional"))
      (node (ref "S1") (pin "4") (pinfunction "NO_2_4") (pintype "bidirectional"))
    )
    (net (code "13") (name "/EN_CHARGE") (class "Default")
      (node (ref "ESP32") (pin "30") (pinfunction "IO18_30") (pintype "bidirectional"))
      (node (ref "R15") (pin "2") (pinfunction "2_2") (pintype "bidirectional"))
    )
    (net (code "14") (name "/G") (class "Default")
      (node (ref "J3") (pin "1") (pinfunction "SLEEVE_1") (pintype "bidirectional"))
      (node (ref "R32") (pin "2") (pinfunction "2_2") (pintype "bidirectional"))
    )
    (net (code "15") (name "/GPIO1") (class "Default")
      (node (ref "IC4") (pin "26") (pinfunction "GPIO1/RCLK1_26") (pintype "bidirectional"))
    )
    (net (code "16") (name "/GPIO2") (class "Default")
      (node (ref "IC4") (pin "25") (pinfunction "GPIO2/RCLK2_25") (pintype "bidirectional"))
    )
    (net (code "17") (name "/GREENLED") (class "Default")
      (node (ref "ESP32") (pin "12") (pinfunction "IO27_12") (pintype "bidirectional"))
      (node (ref "R13") (pin "2") (pinfunction "2_2") (pintype "passive"))
    )
    (net (code "18") (name "/L") (class "Default")
      (node (ref "C14") (pin "2") (pinfunction "2_2") (pintype "bidirectional"))
      (node (ref "J3") (pin "2") (pinfunction "TIP_2") (pintype "bidirectional"))
      (node (ref "R36") (pin "1") (pinfunction "1_1") (pintype "bidirectional"))
    )
    (net (code "19") (name "/R") (class "Default")
      (node (ref "C13") (pin "2") (pinfunction "2_2") (pintype "bidirectional"))
      (node (ref "J3") (pin "3") (pinfunction "RING_3") (pintype "bidirectional"))
      (node (ref "R35") (pin "1") (pinfunction "1_1") (pintype "bidirectional"))
    )
    (net (code "20") (name "/R1") (class "Default")
      (node (ref "IC3") (pin "2") (pinfunction "RI/CLK_2") (pintype "bidirectional"))
    )
    (net (code "21") (name "/REDLED") (class "Default")
      (node (ref "ESP32") (pin "11") (pinfunction "IO26_11") (pintype "bidirectional"))
      (node (ref "R14") (pin "2") (pinfunction "2_2") (pintype "passive"))
    )
    (net (code "22") (name "/RTS") (class "Default")
      (node (ref "IC3") (pin "24") (pinfunction "RTS_24") (pintype "output"))
      (node (ref "Q1") (pin "2") (pinfunction "E_2") (pintype "bidirectional"))
      (node (ref "R5") (pin "1") (pinfunction "1_1") (pintype "bidirectional"))
    )
    (net (code "23") (name "/RXD") (class "Default")
      (node (ref "IC3") (pin "25") (pinfunction "RXD_25") (pintype "input"))
      (node (ref "R2") (pin "2") (pinfunction "2_2") (pintype "bidirectional"))
    )
    (net (code "24") (name "/RXD0") (class "Default")
      (node (ref "ESP32") (pin "34") (pinfunction "RXD0_34") (pintype "bidirectional"))
      (node (ref "R1") (pin "1") (pinfunction "1_1") (pintype "bidirectional"))
    )
    (net (code "25") (name "/SENSOR_VN") (class "Default")
      (node (ref "ESP32") (pin "5") (pinfunction "SENSOR_VN_5") (pintype "bidirectional"))
      (node (ref "R11") (pin "1") (pinfunction "1_1") (pintype "bidirectional"))
      (node (ref "R12") (pin "1") (pinfunction "1_1") (pintype "bidirectional"))
    )
    (net (code "26") (name "/SPI_CS0") (class "Default")
      (node (ref "ESP32") (pin "23") (pinfunction "IO15_23") (pintype "bidirectional"))
      (node (ref "IC4") (pin "18") (pinfunction "~{CS}_18") (pintype "bidirectional"))
    )
    (net (code "27") (name "/SPI_MISO") (class "Default")
      (node (ref "ESP32") (pin "14") (pinfunction "IO12_14") (pintype "bidirectional"))
      (node (ref "IC4") (pin "21") (pinfunction "DOUT_21") (pintype "bidirectional"))
    )
    (net (code "28") (name "/SPI_MOSI") (class "Default")
      (node (ref "ESP32") (pin "16") (pinfunction "IO13_16") (pintype "bidirectional"))
      (node (ref "IC4") (pin "19") (pinfunction "DIN_19") (pintype "bidirectional"))
    )
    (net (code "29") (name "/SPI_SCK") (class "Default")
      (node (ref "ESP32") (pin "13") (pinfunction "IO14_13") (pintype "bidirectional"))
      (node (ref "IC4") (pin "20") (pinfunction "SCLK_20") (pintype "bidirectional"))
    )
    (net (code "30") (name "/TXD") (class "Default")
      (node (ref "IC3") (pin "26") (pinfunction "TXD_26") (pintype "output"))
      (node (ref "R1") (pin "2") (pinfunction "2_2") (pintype "bidirectional"))
    )
    (net (code "31") (name "/TXD0") (class "Default")
      (node (ref "ESP32") (pin "35") (pinfunction "TXD0_35") (pintype "bidirectional"))
      (node (ref "R2") (pin "1") (pinfunction "1_1") (pintype "bidirectional"))
    )
    (net (code "32") (name "/USB_DN") (class "Default")
      (node (ref "D2") (pin "1") (pinfunction "1_1") (pintype "bidirectional"))
      (node (ref "IC3") (pin "5") (pinfunction "D-_5") (pintype "bidirectional"))
      (node (ref "J1") (pin "2") (pinfunction "D-_2") (pintype "bidirectional"))
    )
    (net (code "33") (name "/USB_DP") (class "Default")
      (node (ref "D3") (pin "1") (pinfunction "1_1") (pintype "bidirectional"))
      (node (ref "IC3") (pin "4") (pinfunction "D+_4") (pintype "bidirectional"))
      (node (ref "J1") (pin "3") (pinfunction "D+_3") (pintype "bidirectional"))
    )
    (net (code "34") (name "BAT3.7") (class "Default")
      (node (ref "C7") (pin "1") (pinfunction "+_1") (pintype "bidirectional"))
      (node (ref "D4") (pin "1") (pinfunction "K_1") (pintype "bidirectional"))
      (node (ref "D5") (pin "1") (pinfunction "K_1") (pintype "bidirectional"))
      (node (ref "IC2") (pin "1") (pinfunction "VIN_1") (pintype "bidirectional"))
      (node (ref "IC2") (pin "3") (pinfunction "EN_3") (pintype "bidirectional"))
    )
    (net (code "35") (name "GND") (class "Default")
      (node (ref "C1") (pin "2") (pinfunction "2_2") (pintype "bidirectional"))
      (node (ref "C10") (pin "2") (pinfunction "2_2") (pintype "bidirectional"))
      (node (ref "C11") (pin "2") (pinfunction "-_2") (pintype "bidirectional"))
      (node (ref "C12") (pin "2") (pinfunction "2_2") (pintype "bidirectional"))
      (node (ref "C15") (pin "2") (pinfunction "2_2") (pintype "bidirectional"))
      (node (ref "C16") (pin "2") (pinfunction "2_2") (pintype "bidirectional"))
      (node (ref "C17") (pin "2") (pinfunction "2_2") (pintype "bidirectional"))
      (node (ref "C18") (pin "2") (pinfunction "2_2") (pintype "bidirectional"))
      (node (ref "C19") (pin "2") (pinfunction "2_2") (pintype "bidirectional"))
      (node (ref "C2") (pin "2") (pinfunction "2_2") (pintype "bidirectional"))
      (node (ref "C22") (pin "2") (pinfunction "2_2") (pintype "bidirectional"))
      (node (ref "C23") (pin "2") (pinfunction "2_2") (pintype "bidirectional"))
      (node (ref "C3") (pin "2") (pinfunction "2_2") (pintype "bidirectional"))
      (node (ref "C4") (pin "2") (pinfunction "2_2") (pintype "bidirectional"))
      (node (ref "C5") (pin "2") (pinfunction "2_2") (pintype "bidirectional"))
      (node (ref "C6") (pin "2") (pinfunction "-_2") (pintype "bidirectional"))
      (node (ref "C7") (pin "2") (pinfunction "-_2") (pintype "bidirectional"))
      (node (ref "C8") (pin "2") (pinfunction "2_2") (pintype "bidirectional"))
      (node (ref "C9") (pin "2") (pinfunction "2_2") (pintype "bidirectional"))
      (node (ref "D1") (pin "2") (pinfunction "2_2") (pintype "bidirectional"))
      (node (ref "D2") (pin "2") (pinfunction "2_2") (pintype "bidirectional"))
      (node (ref "D3") (pin "2") (pinfunction "2_2") (pintype "bidirectional"))
      (node (ref "ESP32") (pin "1") (pinfunction "GND_1_1") (pintype "bidirectional"))
      (node (ref "ESP32") (pin "15") (pinfunction "GND_2_15") (pintype "bidirectional"))
      (node (ref "ESP32") (pin "38") (pinfunction "GND_3_38") (pintype "bidirectional"))
      (node (ref "ESP32") (pin "39") (pinfunction "GND_4_39") (pintype "bidirectional"))
      (node (ref "ESP32") (pin "40") (pinfunction "GND_5_40") (pintype "bidirectional"))
      (node (ref "ESP32") (pin "41") (pinfunction "GND_6_41") (pintype "bidirectional"))
      (node (ref "ESP32") (pin "42") (pinfunction "GND_7_42") (pintype "bidirectional"))
      (node (ref "ESP32") (pin "43") (pinfunction "GND_8_43") (pintype "bidirectional"))
      (node (ref "ESP32") (pin "44") (pinfunction "GND_9_44") (pintype "bidirectional"))
      (node (ref "ESP32") (pin "45") (pinfunction "GND_10_45") (pintype "bidirectional"))
      (node (ref "ESP32") (pin "46") (pinfunction "GND_11_46") (pintype "bidirectional"))
      (node (ref "ESP32") (pin "47") (pinfunction "GND_12_47") (pintype "bidirectional"))
      (node (ref "IC2") (pin "2") (pinfunction "GND_2") (pintype "bidirectional"))
      (node (ref "IC2") (pin "4") (pinfunction "ADJ/NC_4") (pintype "bidirectional"))
      (node (ref "IC3") (pin "29") (pinfunction "BGND_29") (pintype "power_in"))
      (node (ref "IC3") (pin "3") (pinfunction "GND_3") (pintype "power_in"))
      (node (ref "IC4") (pin "10") (pinfunction "VREFN_10") (pintype "bidirectional"))
      (node (ref "IC4") (pin "13") (pinfunction "AVSS_13") (pintype "bidirectional"))
      (node (ref "IC4") (pin "24") (pinfunction "DGND_24") (pintype "bidirectional"))
      (node (ref "IC5") (pin "2") (pinfunction "VSS_2") (pintype "bidirectional"))
      (node (ref "J1") (pin "5") (pinfunction "GND_5") (pintype "bidirectional"))
      (node (ref "J1") (pin "6") (pinfunction "6_6") (pintype "bidirectional"))
      (node (ref "J2") (pin "2") (pinfunction "2_2") (pintype "passive"))
      (node (ref "LED1") (pin "3") (pinfunction "RED-_3") (pintype "bidirectional"))
      (node (ref "LED1") (pin "4") (pinfunction "GRN-_4") (pintype "bidirectional"))
      (node (ref "Q4") (pin "1") (pinfunction "E_1") (pintype "bidirectional"))
      (node (ref "R11") (pin "2") (pinfunction "2_2") (pintype "bidirectional"))
      (node (ref "R28") (pin "2") (pinfunction "2_2") (pintype "bidirectional"))
      (node (ref "R3") (pin "2") (pinfunction "2_2") (pintype "bidirectional"))
      (node (ref "R30") (pin "2") (pinfunction "2_2") (pintype "bidirectional"))
      (node (ref "R8") (pin "2") (pinfunction "2_2") (pintype "bidirectional"))
      (node (ref "R9") (pin "1") (pinfunction "1_1") (pintype "bidirectional"))
      (node (ref "S1") (pin "1") (pinfunction "COM_1_1") (pintype "bidirectional"))
      (node (ref "S2") (pin "1") (pinfunction "COM_1_1") (pintype "bidirectional"))
    )
    (net (code "36") (name "Net-(C13-Pad1)") (class "Default")
      (node (ref "C13") (pin "1") (pinfunction "1_1") (pintype "bidirectional"))
      (node (ref "C26") (pin "1") (pinfunction "1_1") (pintype "bidirectional"))
      (node (ref "C28") (pin "2") (pinfunction "2_2") (pintype "bidirectional"))
    )
    (net (code "37") (name "Net-(C14-Pad1)") (class "Default")
      (node (ref "C14") (pin "1") (pinfunction "1_1") (pintype "bidirectional"))
      (node (ref "C27") (pin "1") (pinfunction "1_1") (pintype "bidirectional"))
      (node (ref "C29") (pin "2") (pinfunction "2_2") (pintype "bidirectional"))
    )
    (net (code "38") (name "Net-(C20-Pad2)") (class "Default")
      (node (ref "C20") (pin "2") (pinfunction "2_2") (pintype "bidirectional"))
      (node (ref "R26") (pin "2") (pinfunction "2_2") (pintype "bidirectional"))
      (node (ref "R31") (pin "2") (pinfunction "2_2") (pintype "bidirectional"))
      (node (ref "R32") (pin "1") (pinfunction "1_1") (pintype "bidirectional"))
      (node (ref "R37") (pin "2") (pinfunction "2_2") (pintype "bidirectional"))
    )
    (net (code "39") (name "Net-(C28-Pad1)") (class "Default")
      (node (ref "C28") (pin "1") (pinfunction "1_1") (pintype "bidirectional"))
      (node (ref "R33") (pin "2") (pinfunction "2_2") (pintype "passive"))
    )
    (net (code "40") (name "Net-(C29-Pad1)") (class "Default")
      (node (ref "C29") (pin "1") (pinfunction "1_1") (pintype "bidirectional"))
      (node (ref "R34") (pin "2") (pinfunction "2_2") (pintype "passive"))
    )
    (net (code "41") (name "Net-(D5-A)") (class "Default")
      (node (ref "D5") (pin "2") (pinfunction "A_2") (pintype "bidirectional"))
      (node (ref "S3") (pin "1") (pinfunction "1_1") (pintype "bidirectional"))
    )
    (net (code "42") (name "Net-(IC3-RSTB)") (class "Default")
      (node (ref "IC3") (pin "9") (pinfunction "RSTB_9") (pintype "input"))
      (node (ref "R7") (pin "1") (pinfunction "1_1") (pintype "bidirectional"))
    )
    (net (code "43") (name "Net-(IC3-SUSPENDB)") (class "Default")
      (node (ref "IC3") (pin "11") (pinfunction "SUSPENDB_11") (pintype "output"))
      (node (ref "R3") (pin "1") (pinfunction "1_1") (pintype "bidirectional"))
    )
    (net (code "44") (name "Net-(IC3-VBUS)") (class "Default")
      (node (ref "IC3") (pin "8") (pinfunction "VBUS_8") (pintype "input"))
      (node (ref "R10") (pin "2") (pinfunction "2_2") (pintype "bidirectional"))
      (node (ref "R8") (pin "1") (pinfunction "1_1") (pintype "bidirectional"))
    )
    (net (code "45") (name "Net-(IC4-IN1N)") (class "Default")
      (node (ref "C27") (pin "2") (pinfunction "2_2") (pintype "bidirectional"))
      (node (ref "IC4") (pin "3") (pinfunction "IN1N_3") (pintype "bidirectional"))
      (node (ref "R29") (pin "1") (pinfunction "1_1") (pintype "bidirectional"))
      (node (ref "R30") (pin "1") (pinfunction "1_1") (pintype "bidirectional"))
    )
    (net (code "46") (name "Net-(IC4-IN1P)") (class "Default")
      (node (ref "C26") (pin "2") (pinfunction "2_2") (pintype "bidirectional"))
      (node (ref "IC4") (pin "4") (pinfunction "IN1P_4") (pintype "bidirectional"))
      (node (ref "R27") (pin "1") (pinfunction "1_1") (pintype "bidirectional"))
      (node (ref "R28") (pin "1") (pinfunction "1_1") (pintype "bidirectional"))
    )
    (net (code "47") (name "Net-(IC4-IN2N)") (class "Default")
      (node (ref "IC4") (pin "5") (pinfunction "IN2N_5") (pintype "bidirectional"))
      (node (ref "R36") (pin "2") (pinfunction "2_2") (pintype "bidirectional"))
    )
    (net (code "48") (name "Net-(IC4-IN2P)") (class "Default")
      (node (ref "IC4") (pin "6") (pinfunction "IN2P_6") (pintype "bidirectional"))
      (node (ref "R35") (pin "2") (pinfunction "2_2") (pintype "bidirectional"))
    )
    (net (code "49") (name "Net-(IC4-PGA1N)") (class "Default")
      (node (ref "C21") (pin "2") (pinfunction "2_2") (pintype "passive"))
      (node (ref "IC4") (pin "1") (pinfunction "PGA1N_1") (pintype "bidirectional"))
    )
    (net (code "50") (name "Net-(IC4-PGA1P)") (class "Default")
      (node (ref "C21") (pin "1") (pinfunction "1_1") (pintype "passive"))
      (node (ref "IC4") (pin "2") (pinfunction "PGA1P_2") (pintype "bidirectional"))
    )
    (net (code "51") (name "Net-(IC4-PGA2N)") (class "Default")
      (node (ref "C24") (pin "2") (pinfunction "2_2") (pintype "passive"))
      (node (ref "IC4") (pin "7") (pinfunction "PGA2N_7") (pintype "bidirectional"))
    )
    (net (code "52") (name "Net-(IC4-PGA2P)") (class "Default")
      (node (ref "C24") (pin "1") (pinfunction "1_1") (pintype "passive"))
      (node (ref "IC4") (pin "8") (pinfunction "PGA2P_8") (pintype "bidirectional"))
    )
    (net (code "53") (name "Net-(IC4-RESP_MODN{slash}IN3N)") (class "Default")
      (node (ref "IC4") (pin "32") (pinfunction "RESP_MODN/IN3N_32") (pintype "bidirectional"))
      (node (ref "R34") (pin "1") (pinfunction "1_1") (pintype "passive"))
    )
    (net (code "54") (name "Net-(IC4-RESP_MODP{slash}IN3P)") (class "Default")
      (node (ref "IC4") (pin "31") (pinfunction "RESP_MODP/IN3P_31") (pintype "bidirectional"))
      (node (ref "R33") (pin "1") (pinfunction "1_1") (pintype "passive"))
    )
    (net (code "55") (name "Net-(IC4-RLDINV)") (class "Default")
      (node (ref "C20") (pin "1") (pinfunction "1_1") (pintype "bidirectional"))
      (node (ref "IC4") (pin "28") (pinfunction "RLDINV_28") (pintype "bidirectional"))
      (node (ref "R26") (pin "1") (pinfunction "1_1") (pintype "bidirectional"))
    )
    (net (code "56") (name "Net-(IC4-RLDIN{slash}RLDREF)") (class "Default")
      (node (ref "IC4") (pin "29") (pinfunction "RLDIN/RLDREF_29") (pintype "bidirectional"))
      (node (ref "R31") (pin "1") (pinfunction "1_1") (pintype "bidirectional"))
    )
    (net (code "57") (name "Net-(IC4-RLDOUT)") (class "Default")
      (node (ref "IC4") (pin "30") (pinfunction "RLDOUT_30") (pintype "bidirectional"))
      (node (ref "R37") (pin "1") (pinfunction "1_1") (pintype "bidirectional"))
    )
    (net (code "58") (name "Net-(IC4-VCAP1)") (class "Default")
      (node (ref "C17") (pin "1") (pinfunction "1_1") (pintype "bidirectional"))
      (node (ref "IC4") (pin "11") (pinfunction "VCAP1_11") (pintype "bidirectional"))
    )
    (net (code "59") (name "Net-(IC4-VCAP2)") (class "Default")
      (node (ref "C18") (pin "1") (pinfunction "1_1") (pintype "bidirectional"))
      (node (ref "IC4") (pin "27") (pinfunction "VCAP2_27") (pintype "bidirectional"))
    )
    (net (code "60") (name "Net-(IC4-VREFP)") (class "Default")
      (node (ref "C12") (pin "1") (pinfunction "1_1") (pintype "bidirectional"))
      (node (ref "C19") (pin "1") (pinfunction "1_1") (pintype "bidirectional"))
      (node (ref "IC4") (pin "9") (pinfunction "VREFP_9") (pintype "bidirectional"))
    )
    (net (code "61") (name "Net-(IC5-PROG)") (class "Default")
      (node (ref "IC5") (pin "5") (pinfunction "PROG_5") (pintype "bidirectional"))
      (node (ref "R9") (pin "2") (pinfunction "2_2") (pintype "bidirectional"))
    )
    (net (code "62") (name "Net-(IC5-STAT)") (class "Default")
      (node (ref "IC5") (pin "1") (pinfunction "STAT_1") (pintype "bidirectional"))
      (node (ref "R19") (pin "2") (pinfunction "2_2") (pintype "passive"))
    )
    (net (code "63") (name "Net-(IC5-VDD)") (class "Default")
      (node (ref "C22") (pin "1") (pinfunction "1_1") (pintype "bidirectional"))
      (node (ref "IC5") (pin "4") (pinfunction "VDD_4") (pintype "bidirectional"))
      (node (ref "LED2") (pin "2") (pinfunction "A_2") (pintype "bidirectional"))
      (node (ref "Q3") (pin "3") (pinfunction "D_3") (pintype "bidirectional"))
    )
    (net (code "64") (name "Net-(LED1-GRN+)") (class "Default")
      (node (ref "LED1") (pin "2") (pinfunction "GRN+_2") (pintype "bidirectional"))
      (node (ref "R13") (pin "1") (pinfunction "1_1") (pintype "passive"))
    )
    (net (code "65") (name "Net-(LED1-RED+)") (class "Default")
      (node (ref "LED1") (pin "1") (pinfunction "RED+_1") (pintype "bidirectional"))
      (node (ref "R14") (pin "1") (pinfunction "1_1") (pintype "passive"))
    )
    (net (code "66") (name "Net-(LED2-K)") (class "Default")
      (node (ref "LED2") (pin "1") (pinfunction "K_1") (pintype "bidirectional"))
      (node (ref "R19") (pin "1") (pinfunction "1_1") (pintype "passive"))
    )
    (net (code "67") (name "Net-(Q1-B)") (class "Default")
      (node (ref "Q1") (pin "1") (pinfunction "B_1") (pintype "bidirectional"))
      (node (ref "R4") (pin "2") (pinfunction "2_2") (pintype "bidirectional"))
    )
    (net (code "68") (name "Net-(Q2-B)") (class "Default")
      (node (ref "Q2") (pin "1") (pinfunction "B_1") (pintype "bidirectional"))
      (node (ref "R5") (pin "2") (pinfunction "2_2") (pintype "bidirectional"))
    )
    (net (code "69") (name "Net-(Q3-G)") (class "Default")
      (node (ref "Q3") (pin "1") (pinfunction "G_1") (pintype "bidirectional"))
      (node (ref "R16") (pin "2") (pinfunction "2_2") (pintype "bidirectional"))
      (node (ref "R18") (pin "2") (pinfunction "2_2") (pintype "bidirectional"))
    )
    (net (code "70") (name "Net-(Q4-B)") (class "Default")
      (node (ref "Q4") (pin "3") (pinfunction "B_3") (pintype "bidirectional"))
      (node (ref "R15") (pin "1") (pinfunction "1_1") (pintype "bidirectional"))
    )
    (net (code "71") (name "Net-(Q4-C)") (class "Default")
      (node (ref "Q4") (pin "2") (pinfunction "C_2") (pintype "bidirectional"))
      (node (ref "R18") (pin "1") (pinfunction "1_1") (pintype "bidirectional"))
    )
    (net (code "72") (name "VBUS") (class "Default")
      (node (ref "D1") (pin "1") (pinfunction "1_1") (pintype "bidirectional"))
      (node (ref "D4") (pin "2") (pinfunction "A_2") (pintype "bidirectional"))
      (node (ref "J1") (pin "1") (pinfunction "VBUS_1") (pintype "bidirectional"))
      (node (ref "Q3") (pin "2") (pinfunction "S_2") (pintype "bidirectional"))
      (node (ref "R10") (pin "1") (pinfunction "1_1") (pintype "bidirectional"))
      (node (ref "R16") (pin "1") (pinfunction "1_1") (pintype "bidirectional"))
    )
    (net (code "73") (name "unconnected-(ESP32-IO5-Pad29)") (class "Default")
      (node (ref "ESP32") (pin "29") (pinfunction "IO5_29") (pintype "bidirectional"))
    )
    (net (code "74") (name "unconnected-(ESP32-IO16-Pad27)") (class "Default")
      (node (ref "ESP32") (pin "27") (pinfunction "IO16_27") (pintype "bidirectional"))
    )
    (net (code "75") (name "unconnected-(ESP32-IO17-Pad28)") (class "Default")
      (node (ref "ESP32") (pin "28") (pinfunction "IO17_28") (pintype "bidirectional"))
    )
    (net (code "76") (name "unconnected-(ESP32-IO19-Pad31)") (class "Default")
      (node (ref "ESP32") (pin "31") (pinfunction "IO19_31") (pintype "bidirectional"))
    )
    (net (code "77") (name "unconnected-(ESP32-IO21-Pad33)") (class "Default")
      (node (ref "ESP32") (pin "33") (pinfunction "IO21_33") (pintype "bidirectional"))
    )
    (net (code "78") (name "unconnected-(ESP32-IO22-Pad36)") (class "Default")
      (node (ref "ESP32") (pin "36") (pinfunction "IO22_36") (pintype "bidirectional"))
    )
    (net (code "79") (name "unconnected-(ESP32-IO23-Pad37)") (class "Default")
      (node (ref "ESP32") (pin "37") (pinfunction "IO23_37") (pintype "bidirectional"))
    )
    (net (code "80") (name "unconnected-(ESP32-IO25-Pad10)") (class "Default")
      (node (ref "ESP32") (pin "10") (pinfunction "IO25_10") (pintype "bidirectional"))
    )
    (net (code "81") (name "unconnected-(ESP32-IO32-Pad8)") (class "Default")
      (node (ref "ESP32") (pin "8") (pinfunction "IO32_8") (pintype "bidirectional"))
    )
    (net (code "82") (name "unconnected-(ESP32-IO33-Pad9)") (class "Default")
      (node (ref "ESP32") (pin "9") (pinfunction "IO33_9") (pintype "bidirectional"))
    )
    (net (code "83") (name "unconnected-(ESP32-IO34-Pad6)") (class "Default")
      (node (ref "ESP32") (pin "6") (pinfunction "IO34_6") (pintype "bidirectional"))
    )
    (net (code "84") (name "unconnected-(ESP32-IO35-Pad7)") (class "Default")
      (node (ref "ESP32") (pin "7") (pinfunction "IO35_7") (pintype "bidirectional"))
    )
    (net (code "85") (name "unconnected-(ESP32-NC-Pad32)") (class "Default")
      (node (ref "ESP32") (pin "32") (pinfunction "NC_32") (pintype "no_connect"))
    )
    (net (code "86") (name "unconnected-(ESP32-SCK{slash}CLK-Pad20)") (class "Default")
      (node (ref "ESP32") (pin "20") (pinfunction "SCK/CLK_20") (pintype "bidirectional"))
    )
    (net (code "87") (name "unconnected-(ESP32-SCS{slash}CMD-Pad19)") (class "Default")
      (node (ref "ESP32") (pin "19") (pinfunction "SCS/CMD_19") (pintype "bidirectional"))
    )
    (net (code "88") (name "unconnected-(ESP32-SDI{slash}SD1-Pad22)") (class "Default")
      (node (ref "ESP32") (pin "22") (pinfunction "SDI/SD1_22") (pintype "bidirectional"))
    )
    (net (code "89") (name "unconnected-(ESP32-SDO{slash}SD0-Pad21)") (class "Default")
      (node (ref "ESP32") (pin "21") (pinfunction "SDO/SD0_21") (pintype "bidirectional"))
    )
    (net (code "90") (name "unconnected-(ESP32-SENSOR_VP-Pad4)") (class "Default")
      (node (ref "ESP32") (pin "4") (pinfunction "SENSOR_VP_4") (pintype "bidirectional"))
    )
    (net (code "91") (name "unconnected-(ESP32-SHD{slash}SD2-Pad17)") (class "Default")
      (node (ref "ESP32") (pin "17") (pinfunction "SHD/SD2_17") (pintype "bidirectional"))
    )
    (net (code "92") (name "unconnected-(ESP32-SWP{slash}SD3-Pad18)") (class "Default")
      (node (ref "ESP32") (pin "18") (pinfunction "SWP/SD3_18") (pintype "bidirectional"))
    )
    (net (code "93") (name "unconnected-(IC3-CHR0-Pad15)") (class "Default")
      (node (ref "IC3") (pin "15") (pinfunction "CHR0_15") (pintype "output"))
    )
    (net (code "94") (name "unconnected-(IC3-CHR1-Pad14)") (class "Default")
      (node (ref "IC3") (pin "14") (pinfunction "CHR1_14") (pintype "output"))
    )
    (net (code "95") (name "unconnected-(IC3-CHREN-Pad13)") (class "Default")
      (node (ref "IC3") (pin "13") (pinfunction "CHREN_13") (pintype "output"))
    )
    (net (code "96") (name "unconnected-(IC3-GPIO.0{slash}TXT-Pad19)") (class "Default")
      (node (ref "IC3") (pin "19") (pinfunction "GPIO.0/TXT_19") (pintype "bidirectional"))
    )
    (net (code "97") (name "unconnected-(IC3-GPIO.1{slash}RXT-Pad18)") (class "Default")
      (node (ref "IC3") (pin "18") (pinfunction "GPIO.1/RXT_18") (pintype "bidirectional"))
    )
    (net (code "98") (name "unconnected-(IC3-GPIO.2{slash}RS485-Pad17)") (class "Default")
      (node (ref "IC3") (pin "17") (pinfunction "GPIO.2/RS485_17") (pintype "bidirectional"))
    )
    (net (code "99") (name "unconnected-(IC3-GPIO.3{slash}WAKEUP-Pad16)") (class "Default")
      (node (ref "IC3") (pin "16") (pinfunction "GPIO.3/WAKEUP_16") (pintype "bidirectional"))
    )
    (net (code "100") (name "unconnected-(IC3-GPIO.4-Pad22)") (class "Default")
      (node (ref "IC3") (pin "22") (pinfunction "GPIO.4_22") (pintype "bidirectional"))
    )
    (net (code "101") (name "unconnected-(IC3-GPIO.5-Pad21)") (class "Default")
      (node (ref "IC3") (pin "21") (pinfunction "GPIO.5_21") (pintype "bidirectional"))
    )
    (net (code "102") (name "unconnected-(IC3-GPIO.6-Pad20)") (class "Default")
      (node (ref "IC3") (pin "20") (pinfunction "GPIO.6_20") (pintype "bidirectional"))
    )
    (net (code "103") (name "unconnected-(IC3-NC-Pad10)") (class "Default")
      (node (ref "IC3") (pin "10") (pinfunction "NC_10") (pintype "no_connect"))
    )
    (net (code "104") (name "unconnected-(IC3-SUSPEND-Pad12)") (class "Default")
      (node (ref "IC3") (pin "12") (pinfunction "SUSPEND_12") (pintype "output"))
    )
    (net (code "105") (name "unconnected-(J1-ID-Pad4)") (class "Default")
      (node (ref "J1") (pin "4") (pinfunction "ID_4") (pintype "bidirectional"))
    )
    (net (code "106") (name "unconnected-(J1-Pad7)") (class "Default")
      (node (ref "J1") (pin "7") (pinfunction "7_7") (pintype "bidirectional"))
    )
    (net (code "107") (name "unconnected-(J1-Pad8)") (class "Default")
      (node (ref "J1") (pin "8") (pinfunction "8_8") (pintype "bidirectional"))
    )
    (net (code "108") (name "unconnected-(J1-Pad9)") (class "Default")
      (node (ref "J1") (pin "9") (pinfunction "9_9") (pintype "bidirectional"))
    )
    (net (code "109") (name "unconnected-(J1-Pad10)") (class "Default")
      (node (ref "J1") (pin "10") (pinfunction "10_10") (pintype "bidirectional"))
    )
    (net (code "110") (name "unconnected-(J1-Pad11)") (class "Default")
      (node (ref "J1") (pin "11") (pinfunction "11_11") (pintype "bidirectional"))
    )
    (net (code "111") (name "unconnected-(J3-TIP_SWITCH-Pad4)") (class "Default")
      (node (ref "J3") (pin "4") (pinfunction "TIP_SWITCH_4") (pintype "bidirectional"))
    )
    (net (code "112") (name "unconnected-(S1-COM_2-Pad2)") (class "Default")
      (node (ref "S1") (pin "2") (pinfunction "COM_2_2") (pintype "bidirectional"))
    )
    (net (code "113") (name "unconnected-(S1-NO_1-Pad3)") (class "Default")
      (node (ref "S1") (pin "3") (pinfunction "NO_1_3") (pintype "bidirectional"))
    )
    (net (code "114") (name "unconnected-(S2-COM_2-Pad2)") (class "Default")
      (node (ref "S2") (pin "2") (pinfunction "COM_2_2") (pintype "bidirectional"))
    )
    (net (code "115") (name "unconnected-(S2-NO_1-Pad3)") (class "Default")
      (node (ref "S2") (pin "3") (pinfunction "NO_1_3") (pintype "bidirectional"))
    )
    (net (code "116") (name "unconnected-(S3-NC-Pad2)") (class "Default")
      (node (ref "S3") (pin "2") (pinfunction "NC_2") (pintype "no_connect"))
    )
    (net (code "117") (name "unconnected-(S3-PadMH1)") (class "Default")
      (node (ref "S3") (pin "MH1") (pinfunction "MH1_MH1") (pintype "bidirectional"))
    )
    (net (code "118") (name "unconnected-(S3-PadMH2)") (class "Default")
      (node (ref "S3") (pin "MH2") (pinfunction "MH2_MH2") (pintype "bidirectional"))
    )
  )
)
